# SCH_Hardware-Hack-day-Project_2025-10-19.net
KiCad netlist of a schematic drawn in EasyEDA
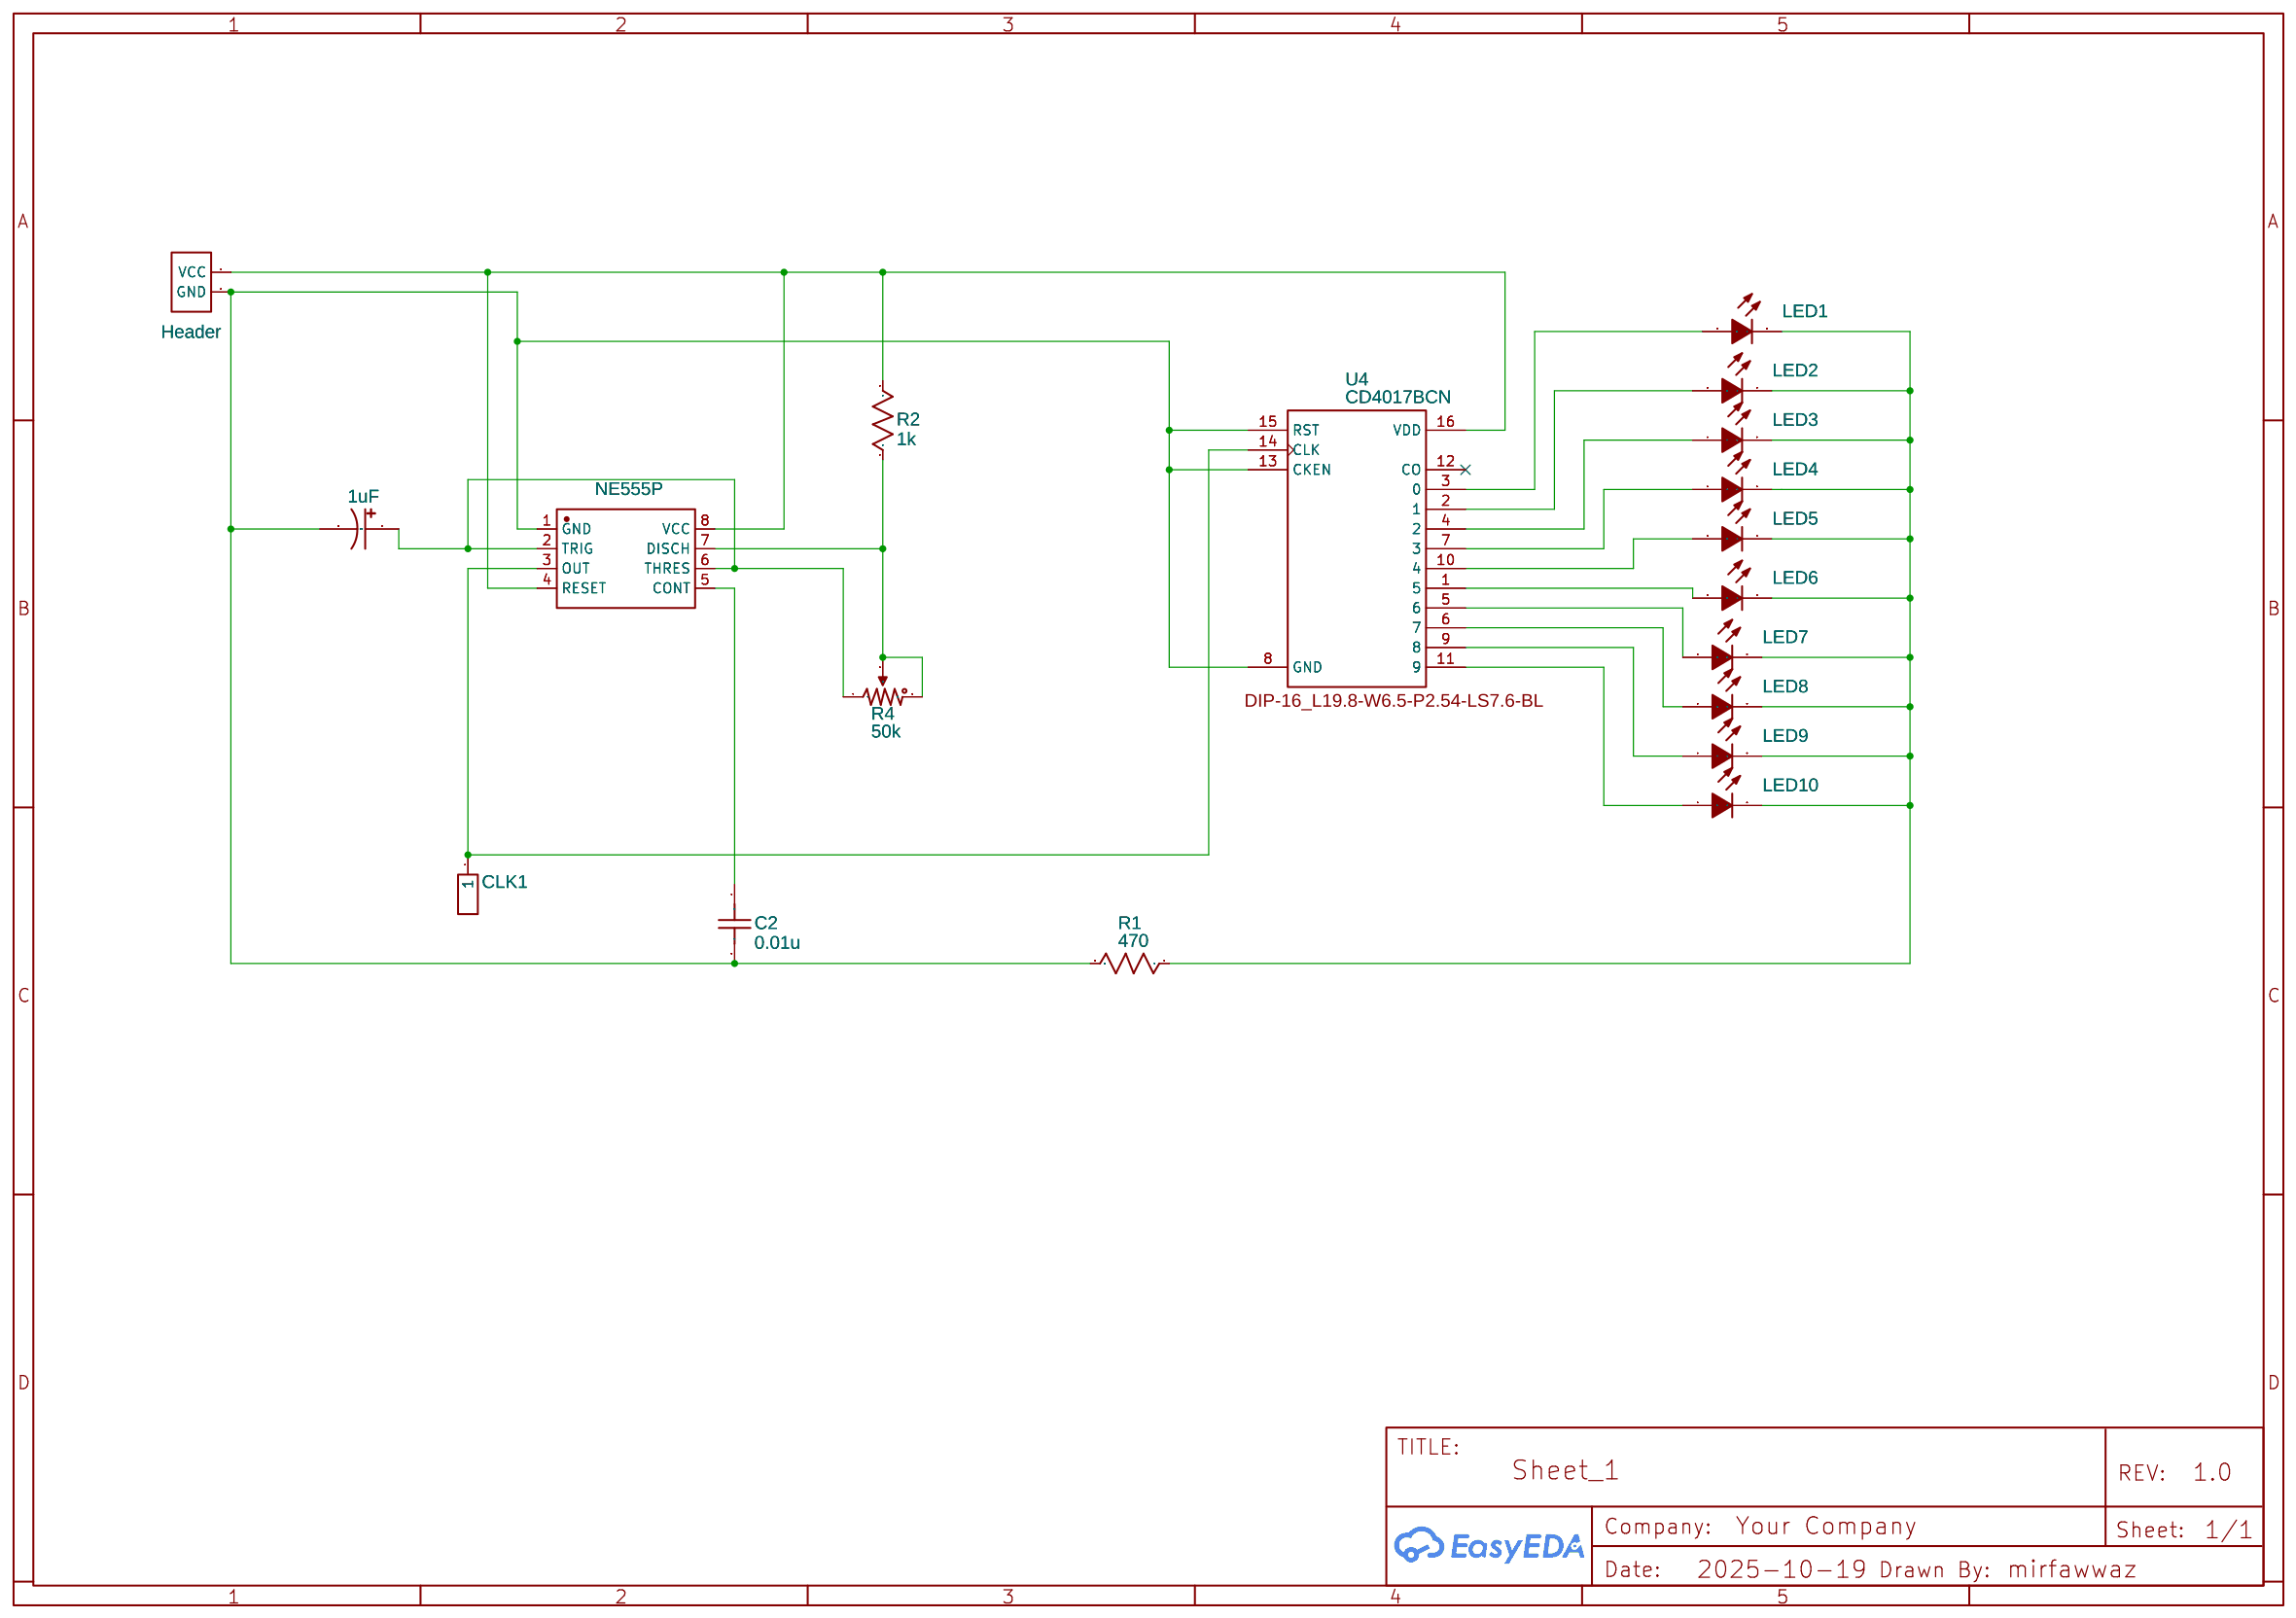
[diagram p0: schematic sheet]

(export (version "E")
  (design (tool "Eeschema 10.0.6"))
  (components
    (comp (ref "C1")
      (value "1uF")
      (fields (field (name "Manufacturer Part") "UVZ1H010MDD") (field (name "Manufacturer") "Nichicon(尼吉康)"))
      (libsource (lib "") (part "UVZ1H010MDD"))
    )
    (comp (ref "C2") (value "0.01u") (libsource (lib "") (part "C_0603_US")))
    (comp (ref "CLK1")
      (value "C81276")
      (fields
        (field (name "Manufacturer Part") "2.54-1*1P针")
        (field (name "Manufacturer") "BOOMELE(Boom Precision Elec)")
      )
      (libsource (lib "") (part "Header-Male-2.54_1x1"))
    )
    (comp (ref "H1") (value "Header") (libsource (lib "") (part "HEADER-FEMALE-2.54_1X2")))
    (comp (ref "LED1") (value "LED_5MM") (libsource (lib "") (part "LED_5MM")))
    (comp (ref "LED2") (value "LED_5MM") (libsource (lib "") (part "LED_5MM")))
    (comp (ref "LED3") (value "LED_5MM") (libsource (lib "") (part "LED_5MM")))
    (comp (ref "LED4") (value "LED_5MM") (libsource (lib "") (part "LED_5MM")))
    (comp (ref "LED5") (value "LED_5MM") (libsource (lib "") (part "LED_5MM")))
    (comp (ref "LED6") (value "LED_5MM") (libsource (lib "") (part "LED_5MM")))
    (comp (ref "LED7") (value "LED_5MM") (libsource (lib "") (part "LED_5MM")))
    (comp (ref "LED8") (value "LED_5MM") (libsource (lib "") (part "LED_5MM")))
    (comp (ref "LED9") (value "LED_5MM") (libsource (lib "") (part "LED_5MM")))
    (comp (ref "LED10") (value "LED_5MM") (libsource (lib "") (part "LED_5MM")))
    (comp (ref "R1")
      (value "470")
      (fields (field (name "Manufacturer Part") "?"))
      (libsource (lib "") (part "Resistor"))
    )
    (comp (ref "R2")
      (value "1k")
      (fields (field (name "Manufacturer Part") "?"))
      (libsource (lib "") (part "Resistor_1"))
    )
    (comp (ref "R4")
      (value "50k")
      (fields (field (name "Manufacturer Part") "?"))
      (libsource (lib "") (part "Potentiometer"))
    )
    (comp (ref "U2")
      (value "NE555P")
      (fields (field (name "Manufacturer") "TI(德州仪器)"))
      (libsource (lib "") (part "NE555P"))
    )
    (comp (ref "U4") (value "CD4017BCN") (libsource (lib "") (part "CD4017BCN")))
  )
  (nets
    (net (code "1") (name "Net-(H1-GND)") (class "Default")
      (node (ref "C1") (pin "2") (pinfunction "2_2") (pintype "unspecified"))
      (node (ref "C2") (pin "2") (pinfunction "2_2") (pintype "unspecified"))
      (node (ref "H1") (pin "2") (pinfunction "GND_2") (pintype "unspecified"))
      (node (ref "R1") (pin "2") (pinfunction "2_2") (pintype "unspecified"))
      (node (ref "U2") (pin "1") (pinfunction "GND_1") (pintype "unspecified"))
      (node (ref "U4") (pin "13") (pinfunction "CKEN_13") (pintype "unspecified"))
      (node (ref "U4") (pin "15") (pinfunction "RST_15") (pintype "unspecified"))
      (node (ref "U4") (pin "8") (pinfunction "GND_8") (pintype "passive"))
    )
    (net (code "2") (name "Net-(H1-VCC)") (class "Default")
      (node (ref "H1") (pin "1") (pinfunction "VCC_1") (pintype "unspecified"))
      (node (ref "R2") (pin "2") (pinfunction "2_2") (pintype "unspecified"))
      (node (ref "U2") (pin "4") (pinfunction "RESET_4") (pintype "unspecified"))
      (node (ref "U2") (pin "8") (pinfunction "VCC_8") (pintype "unspecified"))
      (node (ref "U4") (pin "16") (pinfunction "VDD_16") (pintype "passive"))
    )
    (net (code "3") (name "Net-(LED1-A)") (class "Default")
      (node (ref "LED1") (pin "1") (pinfunction "A_1") (pintype "input"))
      (node (ref "U4") (pin "3") (pinfunction "0_3") (pintype "output"))
    )
    (net (code "4") (name "Net-(LED1-K)") (class "Default")
      (node (ref "LED1") (pin "2") (pinfunction "K_2") (pintype "input"))
      (node (ref "LED10") (pin "2") (pinfunction "K_2") (pintype "input"))
      (node (ref "LED2") (pin "2") (pinfunction "K_2") (pintype "input"))
      (node (ref "LED3") (pin "2") (pinfunction "K_2") (pintype "input"))
      (node (ref "LED4") (pin "2") (pinfunction "K_2") (pintype "input"))
      (node (ref "LED5") (pin "2") (pinfunction "K_2") (pintype "input"))
      (node (ref "LED6") (pin "2") (pinfunction "K_2") (pintype "input"))
      (node (ref "LED7") (pin "2") (pinfunction "K_2") (pintype "input"))
      (node (ref "LED8") (pin "2") (pinfunction "K_2") (pintype "input"))
      (node (ref "LED9") (pin "2") (pinfunction "K_2") (pintype "input"))
      (node (ref "R1") (pin "1") (pinfunction "1_1") (pintype "unspecified"))
    )
    (net (code "5") (name "Net-(LED2-A)") (class "Default")
      (node (ref "LED2") (pin "1") (pinfunction "A_1") (pintype "input"))
      (node (ref "U4") (pin "2") (pinfunction "1_2") (pintype "output"))
    )
    (net (code "6") (name "Net-(LED3-A)") (class "Default")
      (node (ref "LED3") (pin "1") (pinfunction "A_1") (pintype "input"))
      (node (ref "U4") (pin "4") (pinfunction "2_4") (pintype "output"))
    )
    (net (code "7") (name "Net-(LED4-A)") (class "Default")
      (node (ref "LED4") (pin "1") (pinfunction "A_1") (pintype "input"))
      (node (ref "U4") (pin "7") (pinfunction "3_7") (pintype "output"))
    )
    (net (code "8") (name "Net-(LED5-A)") (class "Default")
      (node (ref "LED5") (pin "1") (pinfunction "A_1") (pintype "input"))
      (node (ref "U4") (pin "10") (pinfunction "4_10") (pintype "output"))
    )
    (net (code "9") (name "Net-(LED6-A)") (class "Default")
      (node (ref "LED6") (pin "1") (pinfunction "A_1") (pintype "input"))
      (node (ref "U4") (pin "1") (pinfunction "5_1") (pintype "output"))
    )
    (net (code "10") (name "Net-(LED7-A)") (class "Default")
      (node (ref "LED7") (pin "1") (pinfunction "A_1") (pintype "input"))
      (node (ref "U4") (pin "5") (pinfunction "6_5") (pintype "output"))
    )
    (net (code "11") (name "Net-(LED8-A)") (class "Default")
      (node (ref "LED8") (pin "1") (pinfunction "A_1") (pintype "input"))
      (node (ref "U4") (pin "6") (pinfunction "7_6") (pintype "output"))
    )
    (net (code "12") (name "Net-(LED9-A)") (class "Default")
      (node (ref "LED9") (pin "1") (pinfunction "A_1") (pintype "input"))
      (node (ref "U4") (pin "9") (pinfunction "8_9") (pintype "output"))
    )
    (net (code "13") (name "Net-(LED10-A)") (class "Default")
      (node (ref "LED10") (pin "1") (pinfunction "A_1") (pintype "input"))
      (node (ref "U4") (pin "11") (pinfunction "9_11") (pintype "output"))
    )
    (net (code "14") (name "Net-(R4-2)") (class "Default")
      (node (ref "R2") (pin "1") (pinfunction "1_1") (pintype "unspecified"))
      (node (ref "R4") (pin "2") (pinfunction "3_2") (pintype "unspecified"))
      (node (ref "R4") (pin "3") (pinfunction "2_3") (pintype "unspecified"))
      (node (ref "U2") (pin "7") (pinfunction "DISCH_7") (pintype "unspecified"))
    )
    (net (code "15") (name "Net-(U2-CONT)") (class "Default")
      (node (ref "C2") (pin "1") (pinfunction "1_1") (pintype "unspecified"))
      (node (ref "U2") (pin "5") (pinfunction "CONT_5") (pintype "unspecified"))
    )
    (net (code "16") (name "Net-(U2-OUT)") (class "Default")
      (node (ref "CLK1") (pin "1") (pinfunction "1_1") (pintype "unspecified"))
      (node (ref "U2") (pin "3") (pinfunction "OUT_3") (pintype "unspecified"))
      (node (ref "U4") (pin "14") (pinfunction "CLK_14") (pintype "unspecified"))
    )
    (net (code "17") (name "Net-(U2-THRES)") (class "Default")
      (node (ref "C1") (pin "1") (pinfunction "1_1") (pintype "unspecified"))
      (node (ref "R4") (pin "1") (pinfunction "1_1") (pintype "unspecified"))
      (node (ref "U2") (pin "2") (pinfunction "TRIG_2") (pintype "unspecified"))
      (node (ref "U2") (pin "6") (pinfunction "THRES_6") (pintype "unspecified"))
    )
    (net (code "18") (name "unconnected-(U4-CO-Pad12)") (class "Default")
      (node (ref "U4") (pin "12") (pinfunction "CO_12") (pintype "output+no_connect"))
    )
  )
)
